# Minty_Stick_Amp.net
KiCad netlist of a schematic drawn in EAGLE
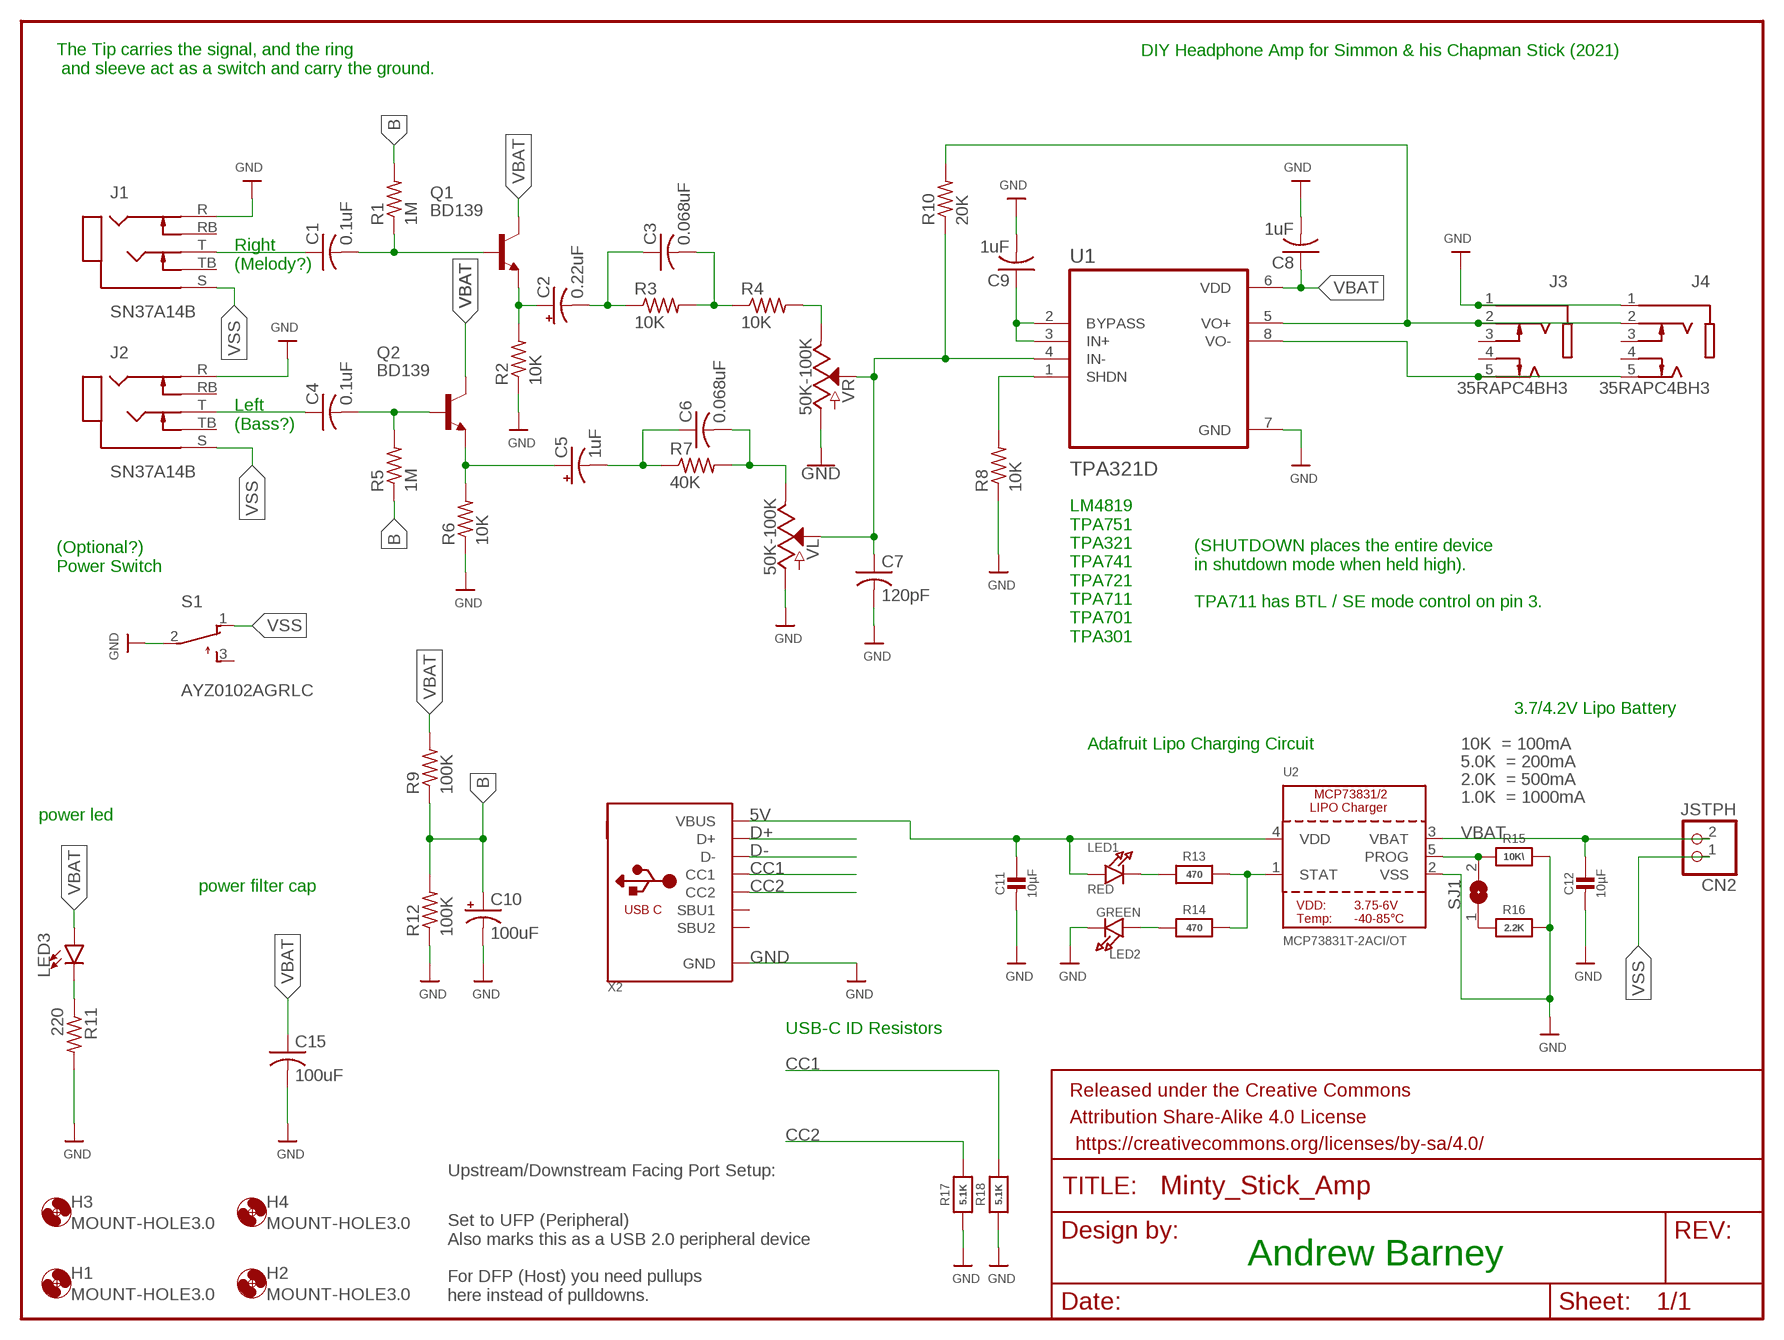
[diagram p0: schematic, sheet 1]

(export (version "E")
  (design (tool "Eeschema 10.0.6"))
  (components
    (comp (ref "C1")
      (value "0.1uF")
      (footprint "eagle-import:C0805K")
      (libsource (lib "eagle-import") (part "C-USC0805K"))
    )
    (comp (ref "C2")
      (value "0.22uF")
      (footprint "eagle-import:E2,5-6")
      (libsource (lib "eagle-import") (part "CPOL-USE2.5-6"))
    )
    (comp (ref "C3")
      (value "0.068uF")
      (footprint "eagle-import:C0805K")
      (libsource (lib "eagle-import") (part "C-USC0805K"))
    )
    (comp (ref "C4")
      (value "0.1uF")
      (footprint "eagle-import:C0805K")
      (libsource (lib "eagle-import") (part "C-USC0805K"))
    )
    (comp (ref "C5")
      (value "1uF")
      (footprint "eagle-import:E2,5-6")
      (libsource (lib "eagle-import") (part "CPOL-USE2.5-6"))
    )
    (comp (ref "C6")
      (value "0.068uF")
      (footprint "eagle-import:C0805K")
      (libsource (lib "eagle-import") (part "C-USC0805K"))
    )
    (comp (ref "C7")
      (value "120pF")
      (footprint "eagle-import:C0805K")
      (libsource (lib "eagle-import") (part "C-USC0805K"))
    )
    (comp (ref "C8")
      (value "1uF")
      (footprint "eagle-import:C0805K")
      (libsource (lib "eagle-import") (part "C-USC0805K"))
    )
    (comp (ref "C9")
      (value "1uF")
      (footprint "eagle-import:C0805K")
      (libsource (lib "eagle-import") (part "C-USC0805K"))
    )
    (comp (ref "C10")
      (value "100uF")
      (footprint "eagle-import:E2,5-6")
      (libsource (lib "eagle-import") (part "CPOL-USE2.5-6"))
    )
    (comp (ref "C11")
      (value "10µF")
      (footprint "eagle-import:_0805")
      (libsource (lib "eagle-import") (part "CAP_CERAMIC_0805"))
    )
    (comp (ref "C12")
      (value "10µF")
      (footprint "eagle-import:_0805")
      (libsource (lib "eagle-import") (part "CAP_CERAMIC_0805"))
    )
    (comp (ref "C15")
      (value "100uF")
      (footprint "eagle-import:C0805K")
      (libsource (lib "eagle-import") (part "C-USC0805K"))
    )
    (comp (ref "CN2")
      (value "JSTPH")
      (footprint "eagle-import:JSTPH2")
      (libsource (lib "eagle-import") (part "JST_2PIN"))
    )
    (comp (ref "FRAME1")
      (value "FRAME-LETTERNO_PACKAGE")
      (footprint "eagle-import:DUMMY")
      (fields (field (name "DESIGNER") "Nobody"))
      (libsource (lib "eagle-import") (part "FRAME-LETTERNO_PACKAGE"))
    )
    (comp (ref "H1")
      (value "MOUNT-HOLE3.0")
      (footprint "eagle-import:3,0")
      (libsource (lib "eagle-import") (part "MOUNT-HOLE3.0"))
    )
    (comp (ref "H2")
      (value "MOUNT-HOLE3.0")
      (footprint "eagle-import:3,0")
      (libsource (lib "eagle-import") (part "MOUNT-HOLE3.0"))
    )
    (comp (ref "H3")
      (value "MOUNT-HOLE3.0")
      (footprint "eagle-import:3,0")
      (libsource (lib "eagle-import") (part "MOUNT-HOLE3.0"))
    )
    (comp (ref "H4")
      (value "MOUNT-HOLE3.0")
      (footprint "eagle-import:3,0")
      (libsource (lib "eagle-import") (part "MOUNT-HOLE3.0"))
    )
    (comp (ref "J1")
      (value "SN37A14B")
      (footprint "eagle-import:SWITCHCRAFT_SN37A14B")
      (fields (field (name "MF") "Switchcraft"))
      (libsource (lib "eagle-import") (part "SN37A14B"))
    )
    (comp (ref "J2")
      (value "SN37A14B")
      (footprint "eagle-import:SWITCHCRAFT_SN37A14B")
      (fields (field (name "MF") "Switchcraft"))
      (libsource (lib "eagle-import") (part "SN37A14B"))
    )
    (comp (ref "J3")
      (value "35RAPC4BH3")
      (footprint "eagle-import:SWITCHCRAFT_35RAPC4BH3")
      (fields (field (name "MF") "Switchcraft Inc."))
      (libsource (lib "eagle-import") (part "35RAPC4BH3"))
    )
    (comp (ref "J4")
      (value "35RAPC4BH3")
      (footprint "eagle-import:SWITCHCRAFT_35RAPC4BH3")
      (fields (field (name "MF") "Switchcraft Inc."))
      (libsource (lib "eagle-import") (part "35RAPC4BH3"))
    )
    (comp (ref "LED1")
      (value "RED")
      (footprint "eagle-import:CHIPLED_0805")
      (libsource (lib "eagle-import") (part "LED0805"))
    )
    (comp (ref "LED2")
      (value "GREEN")
      (footprint "eagle-import:CHIPLED_0805")
      (libsource (lib "eagle-import") (part "LED0805"))
    )
    (comp (ref "LED3")
      (value "LED3MM")
      (footprint "eagle-import:LED_3MM")
      (libsource (lib "eagle-import") (part "LED3MM"))
    )
    (comp (ref "Q1")
      (value "BD139")
      (footprint "eagle-import:TO126-V")
      (libsource (lib "eagle-import") (part "BD139"))
    )
    (comp (ref "Q2")
      (value "BD139")
      (footprint "eagle-import:TO126-V")
      (libsource (lib "eagle-import") (part "BD139"))
    )
    (comp (ref "R1")
      (value "1M")
      (footprint "eagle-import:M0805")
      (libsource (lib "eagle-import") (part "R-US_M0805"))
    )
    (comp (ref "R2")
      (value "10K")
      (footprint "eagle-import:M0805")
      (libsource (lib "eagle-import") (part "R-US_M0805"))
    )
    (comp (ref "R3")
      (value "10K")
      (footprint "eagle-import:M0805")
      (libsource (lib "eagle-import") (part "R-US_M0805"))
    )
    (comp (ref "R4")
      (value "10K")
      (footprint "eagle-import:M0805")
      (libsource (lib "eagle-import") (part "R-US_M0805"))
    )
    (comp (ref "R5")
      (value "1M")
      (footprint "eagle-import:M0805")
      (libsource (lib "eagle-import") (part "R-US_M0805"))
    )
    (comp (ref "R6")
      (value "10K")
      (footprint "eagle-import:M0805")
      (libsource (lib "eagle-import") (part "R-US_M0805"))
    )
    (comp (ref "R7")
      (value "40K")
      (footprint "eagle-import:M0805")
      (libsource (lib "eagle-import") (part "R-US_M0805"))
    )
    (comp (ref "R8")
      (value "10K")
      (footprint "eagle-import:M0805")
      (libsource (lib "eagle-import") (part "R-US_M0805"))
    )
    (comp (ref "R9")
      (value "100K")
      (footprint "eagle-import:M0805")
      (libsource (lib "eagle-import") (part "R-US_M0805"))
    )
    (comp (ref "R10")
      (value "20K")
      (footprint "eagle-import:M0805")
      (libsource (lib "eagle-import") (part "R-US_M0805"))
    )
    (comp (ref "R11")
      (value "220")
      (footprint "eagle-import:0805-THM-7")
      (libsource (lib "eagle-import") (part "R-US_FLIPFLOP7"))
    )
    (comp (ref "R12")
      (value "100K")
      (footprint "eagle-import:M0805")
      (libsource (lib "eagle-import") (part "R-US_M0805"))
    )
    (comp (ref "R13")
      (value "470")
      (footprint "eagle-import:_0805")
      (libsource (lib "eagle-import") (part "RESISTOR_0805"))
    )
    (comp (ref "R14")
      (value "470")
      (footprint "eagle-import:_0805")
      (libsource (lib "eagle-import") (part "RESISTOR_0805"))
    )
    (comp (ref "R15")
      (value "10K\\")
      (footprint "eagle-import:_0805")
      (libsource (lib "eagle-import") (part "RESISTOR_0805"))
    )
    (comp (ref "R16")
      (value "2.2K")
      (footprint "eagle-import:_0805")
      (libsource (lib "eagle-import") (part "RESISTOR_0805"))
    )
    (comp (ref "R17")
      (value "5.1K")
      (footprint "eagle-import:_0805")
      (libsource (lib "eagle-import") (part "RESISTOR_0805"))
    )
    (comp (ref "R18")
      (value "5.1K")
      (footprint "eagle-import:_0805")
      (libsource (lib "eagle-import") (part "RESISTOR_0805"))
    )
    (comp (ref "S1")
      (value "AYZ0102AGRLC")
      (footprint "eagle-import:AYZ0102AGRLC")
      (fields
        (field (name "DIGIKEY_PARTNO") "401-2012-1-ND")
        (field (name "MANUFACTURER") "C&K")
        (field (name "CREATED_BY") "PCBLayout.com")
      )
      (libsource (lib "eagle-import") (part "AYZ0102AGRLC"))
    )
    (comp (ref "SJ1")
      (value "SOLDERJUMPER")
      (footprint "eagle-import:SOLDERJUMPER_ARROW_NOPASTE")
      (libsource (lib "eagle-import") (part "SOLDERJUMPER"))
    )
    (comp (ref "U1")
      (value "TPA321D")
      (footprint "eagle-import:SOIC127P599X175-8N")
      (fields (field (name "MF") "Texas Instruments"))
      (libsource (lib "eagle-import") (part "TPA321D"))
    )
    (comp (ref "U2")
      (value "MCP73831T-2ACI/OT")
      (footprint "eagle-import:SOT23-5")
      (libsource (lib "eagle-import") (part "MCP73831/2"))
    )
    (comp (ref "VL")
      (value "50K-100K")
      (footprint "eagle-import:POT-PTH-ALPS-KIT")
      (libsource (lib "eagle-import") (part "POTENTIOMETER-PTH-9MM-1/20W-20%-KIT"))
    )
    (comp (ref "VR")
      (value "50K-100K")
      (footprint "eagle-import:POT-PTH-ALPS-KIT")
      (libsource (lib "eagle-import") (part "POTENTIOMETER-PTH-9MM-1/20W-20%-KIT"))
    )
    (comp (ref "X2")
      (value "USB_C")
      (footprint "eagle-import:USB_C_CUSB31-CFM2AX-01-X")
      (libsource (lib "eagle-import") (part "USB_C"))
    )
  )
  (nets
    (net (code "1") (name "/5V") (class "Default")
      (node (ref "C11") (pin "1") (pinfunction "1_1") (pintype "passive"))
      (node (ref "LED1") (pin "A") (pinfunction "A_A") (pintype "passive"))
      (node (ref "U2") (pin "4") (pinfunction "VDD_4") (pintype "power_in"))
      (node (ref "X2") (pin "A4B9") (pinfunction "VBUS_A4B9") (pintype "power_in"))
      (node (ref "X2") (pin "B4A9") (pinfunction "VBUS_B4A9") (pintype "power_in"))
    )
    (net (code "2") (name "/CC1") (class "Default")
      (node (ref "R18") (pin "2") (pinfunction "2_2") (pintype "passive"))
      (node (ref "X2") (pin "A5") (pinfunction "CC1_A5") (pintype "bidirectional"))
    )
    (net (code "3") (name "/CC2") (class "Default")
      (node (ref "R17") (pin "2") (pinfunction "2_2") (pintype "passive"))
      (node (ref "X2") (pin "B5") (pinfunction "CC2_B5") (pintype "bidirectional"))
    )
    (net (code "4") (name "/D+") (class "Default")
      (node (ref "X2") (pin "A6") (pinfunction "D+_A6") (pintype "bidirectional"))
      (node (ref "X2") (pin "B6") (pinfunction "D+_B6") (pintype "bidirectional"))
    )
    (net (code "5") (name "/D-") (class "Default")
      (node (ref "X2") (pin "A7") (pinfunction "D-_A7") (pintype "bidirectional"))
      (node (ref "X2") (pin "B7") (pinfunction "D-_B7") (pintype "bidirectional"))
    )
    (net (code "6") (name "B") (class "Default")
      (node (ref "C10") (pin "+") (pinfunction "+_+") (pintype "passive"))
      (node (ref "R1") (pin "2") (pinfunction "2_2") (pintype "passive"))
      (node (ref "R12") (pin "2") (pinfunction "2_2") (pintype "passive"))
      (node (ref "R5") (pin "1") (pinfunction "1_1") (pintype "passive"))
      (node (ref "R9") (pin "1") (pinfunction "1_1") (pintype "passive"))
    )
    (net (code "7") (name "GND") (class "Default")
      (node (ref "C10") (pin "-") (pinfunction "-_-") (pintype "passive"))
      (node (ref "C11") (pin "2") (pinfunction "2_2") (pintype "passive"))
      (node (ref "C12") (pin "2") (pinfunction "2_2") (pintype "passive"))
      (node (ref "C15") (pin "2") (pinfunction "2_2") (pintype "passive"))
      (node (ref "C7") (pin "2") (pinfunction "2_2") (pintype "passive"))
      (node (ref "C8") (pin "2") (pinfunction "2_2") (pintype "passive"))
      (node (ref "C9") (pin "2") (pinfunction "2_2") (pintype "passive"))
      (node (ref "J1") (pin "R") (pinfunction "R_R") (pintype "passive"))
      (node (ref "J2") (pin "R") (pinfunction "R_R") (pintype "passive"))
      (node (ref "J3") (pin "1") (pinfunction "1_1") (pintype "passive"))
      (node (ref "J4") (pin "1") (pinfunction "1_1") (pintype "passive"))
      (node (ref "LED2") (pin "C") (pinfunction "C_C") (pintype "passive"))
      (node (ref "R11") (pin "2") (pinfunction "2_2") (pintype "passive"))
      (node (ref "R12") (pin "1") (pinfunction "1_1") (pintype "passive"))
      (node (ref "R15") (pin "2") (pinfunction "2_2") (pintype "passive"))
      (node (ref "R16") (pin "2") (pinfunction "2_2") (pintype "passive"))
      (node (ref "R17") (pin "1") (pinfunction "1_1") (pintype "passive"))
      (node (ref "R18") (pin "1") (pinfunction "1_1") (pintype "passive"))
      (node (ref "R2") (pin "1") (pinfunction "1_1") (pintype "passive"))
      (node (ref "R6") (pin "1") (pinfunction "1_1") (pintype "passive"))
      (node (ref "R8") (pin "1") (pinfunction "1_1") (pintype "passive"))
      (node (ref "S1") (pin "2") (pinfunction "2_2") (pintype "passive"))
      (node (ref "U1") (pin "7") (pinfunction "GND_7") (pintype "power_in"))
      (node (ref "U2") (pin "2") (pinfunction "VSS_2") (pintype "power_in"))
      (node (ref "VL") (pin "P$3") (pinfunction "A_P$3") (pintype "passive"))
      (node (ref "VR") (pin "P$3") (pinfunction "A_P$3") (pintype "passive"))
      (node (ref "X2") (pin "A1B12") (pinfunction "GND_A1B12") (pintype "power_in"))
      (node (ref "X2") (pin "B1A12") (pinfunction "GND_B1A12") (pintype "power_in"))
    )
    (net (code "8") (name "Net-(C1-Pad1)") (class "Default")
      (node (ref "C1") (pin "1") (pinfunction "1_1") (pintype "passive"))
      (node (ref "J1") (pin "T") (pinfunction "T_T") (pintype "passive"))
    )
    (net (code "9") (name "Net-(C1-Pad2)") (class "Default")
      (node (ref "C1") (pin "2") (pinfunction "2_2") (pintype "passive"))
      (node (ref "Q1") (pin "B") (pinfunction "B_B") (pintype "passive"))
      (node (ref "R1") (pin "1") (pinfunction "1_1") (pintype "passive"))
    )
    (net (code "10") (name "Net-(C2-Pad+)") (class "Default")
      (node (ref "C2") (pin "+") (pinfunction "+_+") (pintype "passive"))
      (node (ref "Q1") (pin "E") (pinfunction "E_E") (pintype "passive"))
      (node (ref "R2") (pin "2") (pinfunction "2_2") (pintype "passive"))
    )
    (net (code "11") (name "Net-(C2-Pad-)") (class "Default")
      (node (ref "C2") (pin "-") (pinfunction "-_-") (pintype "passive"))
      (node (ref "C3") (pin "1") (pinfunction "1_1") (pintype "passive"))
      (node (ref "R3") (pin "1") (pinfunction "1_1") (pintype "passive"))
    )
    (net (code "12") (name "Net-(C3-Pad2)") (class "Default")
      (node (ref "C3") (pin "2") (pinfunction "2_2") (pintype "passive"))
      (node (ref "R3") (pin "2") (pinfunction "2_2") (pintype "passive"))
      (node (ref "R4") (pin "1") (pinfunction "1_1") (pintype "passive"))
    )
    (net (code "13") (name "Net-(C4-Pad1)") (class "Default")
      (node (ref "C4") (pin "1") (pinfunction "1_1") (pintype "passive"))
      (node (ref "J2") (pin "T") (pinfunction "T_T") (pintype "passive"))
    )
    (net (code "14") (name "Net-(C4-Pad2)") (class "Default")
      (node (ref "C4") (pin "2") (pinfunction "2_2") (pintype "passive"))
      (node (ref "Q2") (pin "B") (pinfunction "B_B") (pintype "passive"))
      (node (ref "R5") (pin "2") (pinfunction "2_2") (pintype "passive"))
    )
    (net (code "15") (name "Net-(C5-Pad+)") (class "Default")
      (node (ref "C5") (pin "+") (pinfunction "+_+") (pintype "passive"))
      (node (ref "Q2") (pin "E") (pinfunction "E_E") (pintype "passive"))
      (node (ref "R6") (pin "2") (pinfunction "2_2") (pintype "passive"))
    )
    (net (code "16") (name "Net-(C5-Pad-)") (class "Default")
      (node (ref "C5") (pin "-") (pinfunction "-_-") (pintype "passive"))
      (node (ref "C6") (pin "1") (pinfunction "1_1") (pintype "passive"))
      (node (ref "R7") (pin "1") (pinfunction "1_1") (pintype "passive"))
    )
    (net (code "17") (name "Net-(LED1-PadC)") (class "Default")
      (node (ref "LED1") (pin "C") (pinfunction "C_C") (pintype "passive"))
      (node (ref "R13") (pin "1") (pinfunction "1_1") (pintype "passive"))
    )
    (net (code "18") (name "Net-(LED2-PadA)") (class "Default")
      (node (ref "LED2") (pin "A") (pinfunction "A_A") (pintype "passive"))
      (node (ref "R14") (pin "1") (pinfunction "1_1") (pintype "passive"))
    )
    (net (code "19") (name "Net-(LED3-C)") (class "Default")
      (node (ref "LED3") (pin "K") (pinfunction "C_K") (pintype "passive"))
      (node (ref "R11") (pin "1") (pinfunction "1_1") (pintype "passive"))
    )
    (net (code "20") (name "Net-(R16-Pad1)") (class "Default")
      (node (ref "R16") (pin "1") (pinfunction "1_1") (pintype "passive"))
      (node (ref "SJ1") (pin "1") (pinfunction "1_1") (pintype "passive"))
    )
    (net (code "21") (name "Net-(U1-BYPASS)") (class "Default")
      (node (ref "C9") (pin "1") (pinfunction "1_1") (pintype "passive"))
      (node (ref "U1") (pin "2") (pinfunction "BYPASS_2") (pintype "input"))
      (node (ref "U1") (pin "3") (pinfunction "IN+_3") (pintype "input"))
    )
    (net (code "22") (name "Net-(U1-IN-)") (class "Default")
      (node (ref "C7") (pin "1") (pinfunction "1_1") (pintype "passive"))
      (node (ref "R10") (pin "1") (pinfunction "1_1") (pintype "passive"))
      (node (ref "U1") (pin "4") (pinfunction "IN-_4") (pintype "input"))
      (node (ref "VL") (pin "P$2") (pinfunction "S_P$2") (pintype "passive"))
      (node (ref "VR") (pin "P$2") (pinfunction "S_P$2") (pintype "passive"))
    )
    (net (code "23") (name "Net-(U1-SHDN)") (class "Default")
      (node (ref "R8") (pin "2") (pinfunction "2_2") (pintype "passive"))
      (node (ref "U1") (pin "1") (pinfunction "SHDN_1") (pintype "input"))
    )
    (net (code "24") (name "Net-(U1-VO+)") (class "Default")
      (node (ref "J3") (pin "2") (pinfunction "2_2") (pintype "passive"))
      (node (ref "J4") (pin "2") (pinfunction "2_2") (pintype "passive"))
      (node (ref "R10") (pin "2") (pinfunction "2_2") (pintype "passive"))
      (node (ref "U1") (pin "5") (pinfunction "VO+_5") (pintype "output"))
    )
    (net (code "25") (name "Net-(U1-VO-)") (class "Default")
      (node (ref "J3") (pin "5") (pinfunction "5_5") (pintype "passive"))
      (node (ref "J4") (pin "5") (pinfunction "5_5") (pintype "passive"))
      (node (ref "U1") (pin "8") (pinfunction "VO-_8") (pintype "output"))
    )
    (net (code "26") (name "Net-(U2-PROG)") (class "Default")
      (node (ref "R15") (pin "1") (pinfunction "1_1") (pintype "passive"))
      (node (ref "SJ1") (pin "2") (pinfunction "2_2") (pintype "passive"))
      (node (ref "U2") (pin "5") (pinfunction "PROG_5") (pintype "input"))
    )
    (net (code "27") (name "Net-(U2-STAT)") (class "Default")
      (node (ref "R13") (pin "2") (pinfunction "2_2") (pintype "passive"))
      (node (ref "R14") (pin "2") (pinfunction "2_2") (pintype "passive"))
      (node (ref "U2") (pin "1") (pinfunction "STAT_1") (pintype "output"))
    )
    (net (code "28") (name "Net-(VL-E)") (class "Default")
      (node (ref "C6") (pin "2") (pinfunction "2_2") (pintype "passive"))
      (node (ref "R7") (pin "2") (pinfunction "2_2") (pintype "passive"))
      (node (ref "VL") (pin "P$1") (pinfunction "E_P$1") (pintype "passive"))
    )
    (net (code "29") (name "Net-(VR-E)") (class "Default")
      (node (ref "R4") (pin "2") (pinfunction "2_2") (pintype "passive"))
      (node (ref "VR") (pin "P$1") (pinfunction "E_P$1") (pintype "passive"))
    )
    (net (code "30") (name "VBAT") (class "Default")
      (node (ref "C12") (pin "1") (pinfunction "1_1") (pintype "passive"))
      (node (ref "C15") (pin "1") (pinfunction "1_1") (pintype "passive"))
      (node (ref "C8") (pin "1") (pinfunction "1_1") (pintype "passive"))
      (node (ref "CN2") (pin "2") (pinfunction "2_2") (pintype "passive"))
      (node (ref "LED3") (pin "A") (pinfunction "A_A") (pintype "passive"))
      (node (ref "Q1") (pin "C") (pinfunction "C_C") (pintype "passive"))
      (node (ref "Q2") (pin "C") (pinfunction "C_C") (pintype "passive"))
      (node (ref "R9") (pin "2") (pinfunction "2_2") (pintype "passive"))
      (node (ref "U1") (pin "6") (pinfunction "VDD_6") (pintype "power_in"))
      (node (ref "U2") (pin "3") (pinfunction "VBAT_3") (pintype "power_in"))
    )
    (net (code "31") (name "VSS") (class "Default")
      (node (ref "CN2") (pin "1") (pinfunction "1_1") (pintype "passive"))
      (node (ref "J1") (pin "S") (pinfunction "S_S") (pintype "passive"))
      (node (ref "J2") (pin "S") (pinfunction "S_S") (pintype "passive"))
      (node (ref "S1") (pin "1") (pinfunction "1_1") (pintype "passive"))
    )
    (net (code "32") (name "unconnected-(J1-PadRB)") (class "Default")
      (node (ref "J1") (pin "RB") (pinfunction "RB_RB") (pintype "passive"))
    )
    (net (code "33") (name "unconnected-(J1-PadTB)") (class "Default")
      (node (ref "J1") (pin "TB") (pinfunction "TB_TB") (pintype "passive"))
    )
    (net (code "34") (name "unconnected-(J2-PadRB)") (class "Default")
      (node (ref "J2") (pin "RB") (pinfunction "RB_RB") (pintype "passive"))
    )
    (net (code "35") (name "unconnected-(J2-PadTB)") (class "Default")
      (node (ref "J2") (pin "TB") (pinfunction "TB_TB") (pintype "passive"))
    )
    (net (code "36") (name "unconnected-(J3-Pad3)") (class "Default")
      (node (ref "J3") (pin "3") (pinfunction "3_3") (pintype "passive"))
    )
    (net (code "37") (name "unconnected-(J3-Pad4)") (class "Default")
      (node (ref "J3") (pin "4") (pinfunction "4_4") (pintype "passive"))
    )
    (net (code "38") (name "unconnected-(J4-Pad3)") (class "Default")
      (node (ref "J4") (pin "3") (pinfunction "3_3") (pintype "passive"))
    )
    (net (code "39") (name "unconnected-(J4-Pad4)") (class "Default")
      (node (ref "J4") (pin "4") (pinfunction "4_4") (pintype "passive"))
    )
    (net (code "40") (name "unconnected-(Q1-PadC2)") (class "Default")
      (node (ref "Q1") (pin "C2") (pinfunction "C2_C2") (pintype "passive"))
    )
    (net (code "41") (name "unconnected-(Q2-PadC2)") (class "Default")
      (node (ref "Q2") (pin "C2") (pinfunction "C2_C2") (pintype "passive"))
    )
    (net (code "42") (name "unconnected-(S1-Pad3)") (class "Default")
      (node (ref "S1") (pin "3") (pinfunction "3_3") (pintype "passive"))
    )
    (net (code "43") (name "unconnected-(X2-SBU1-PadA8)") (class "Default")
      (node (ref "X2") (pin "A8") (pinfunction "SBU1_A8") (pintype "bidirectional"))
    )
    (net (code "44") (name "unconnected-(X2-SBU2-PadB8)") (class "Default")
      (node (ref "X2") (pin "B8") (pinfunction "SBU2_B8") (pintype "bidirectional"))
    )
  )
)
